# ArduinoNano33Proto-V2_0.net
KiCad netlist of a schematic drawn in EAGLE
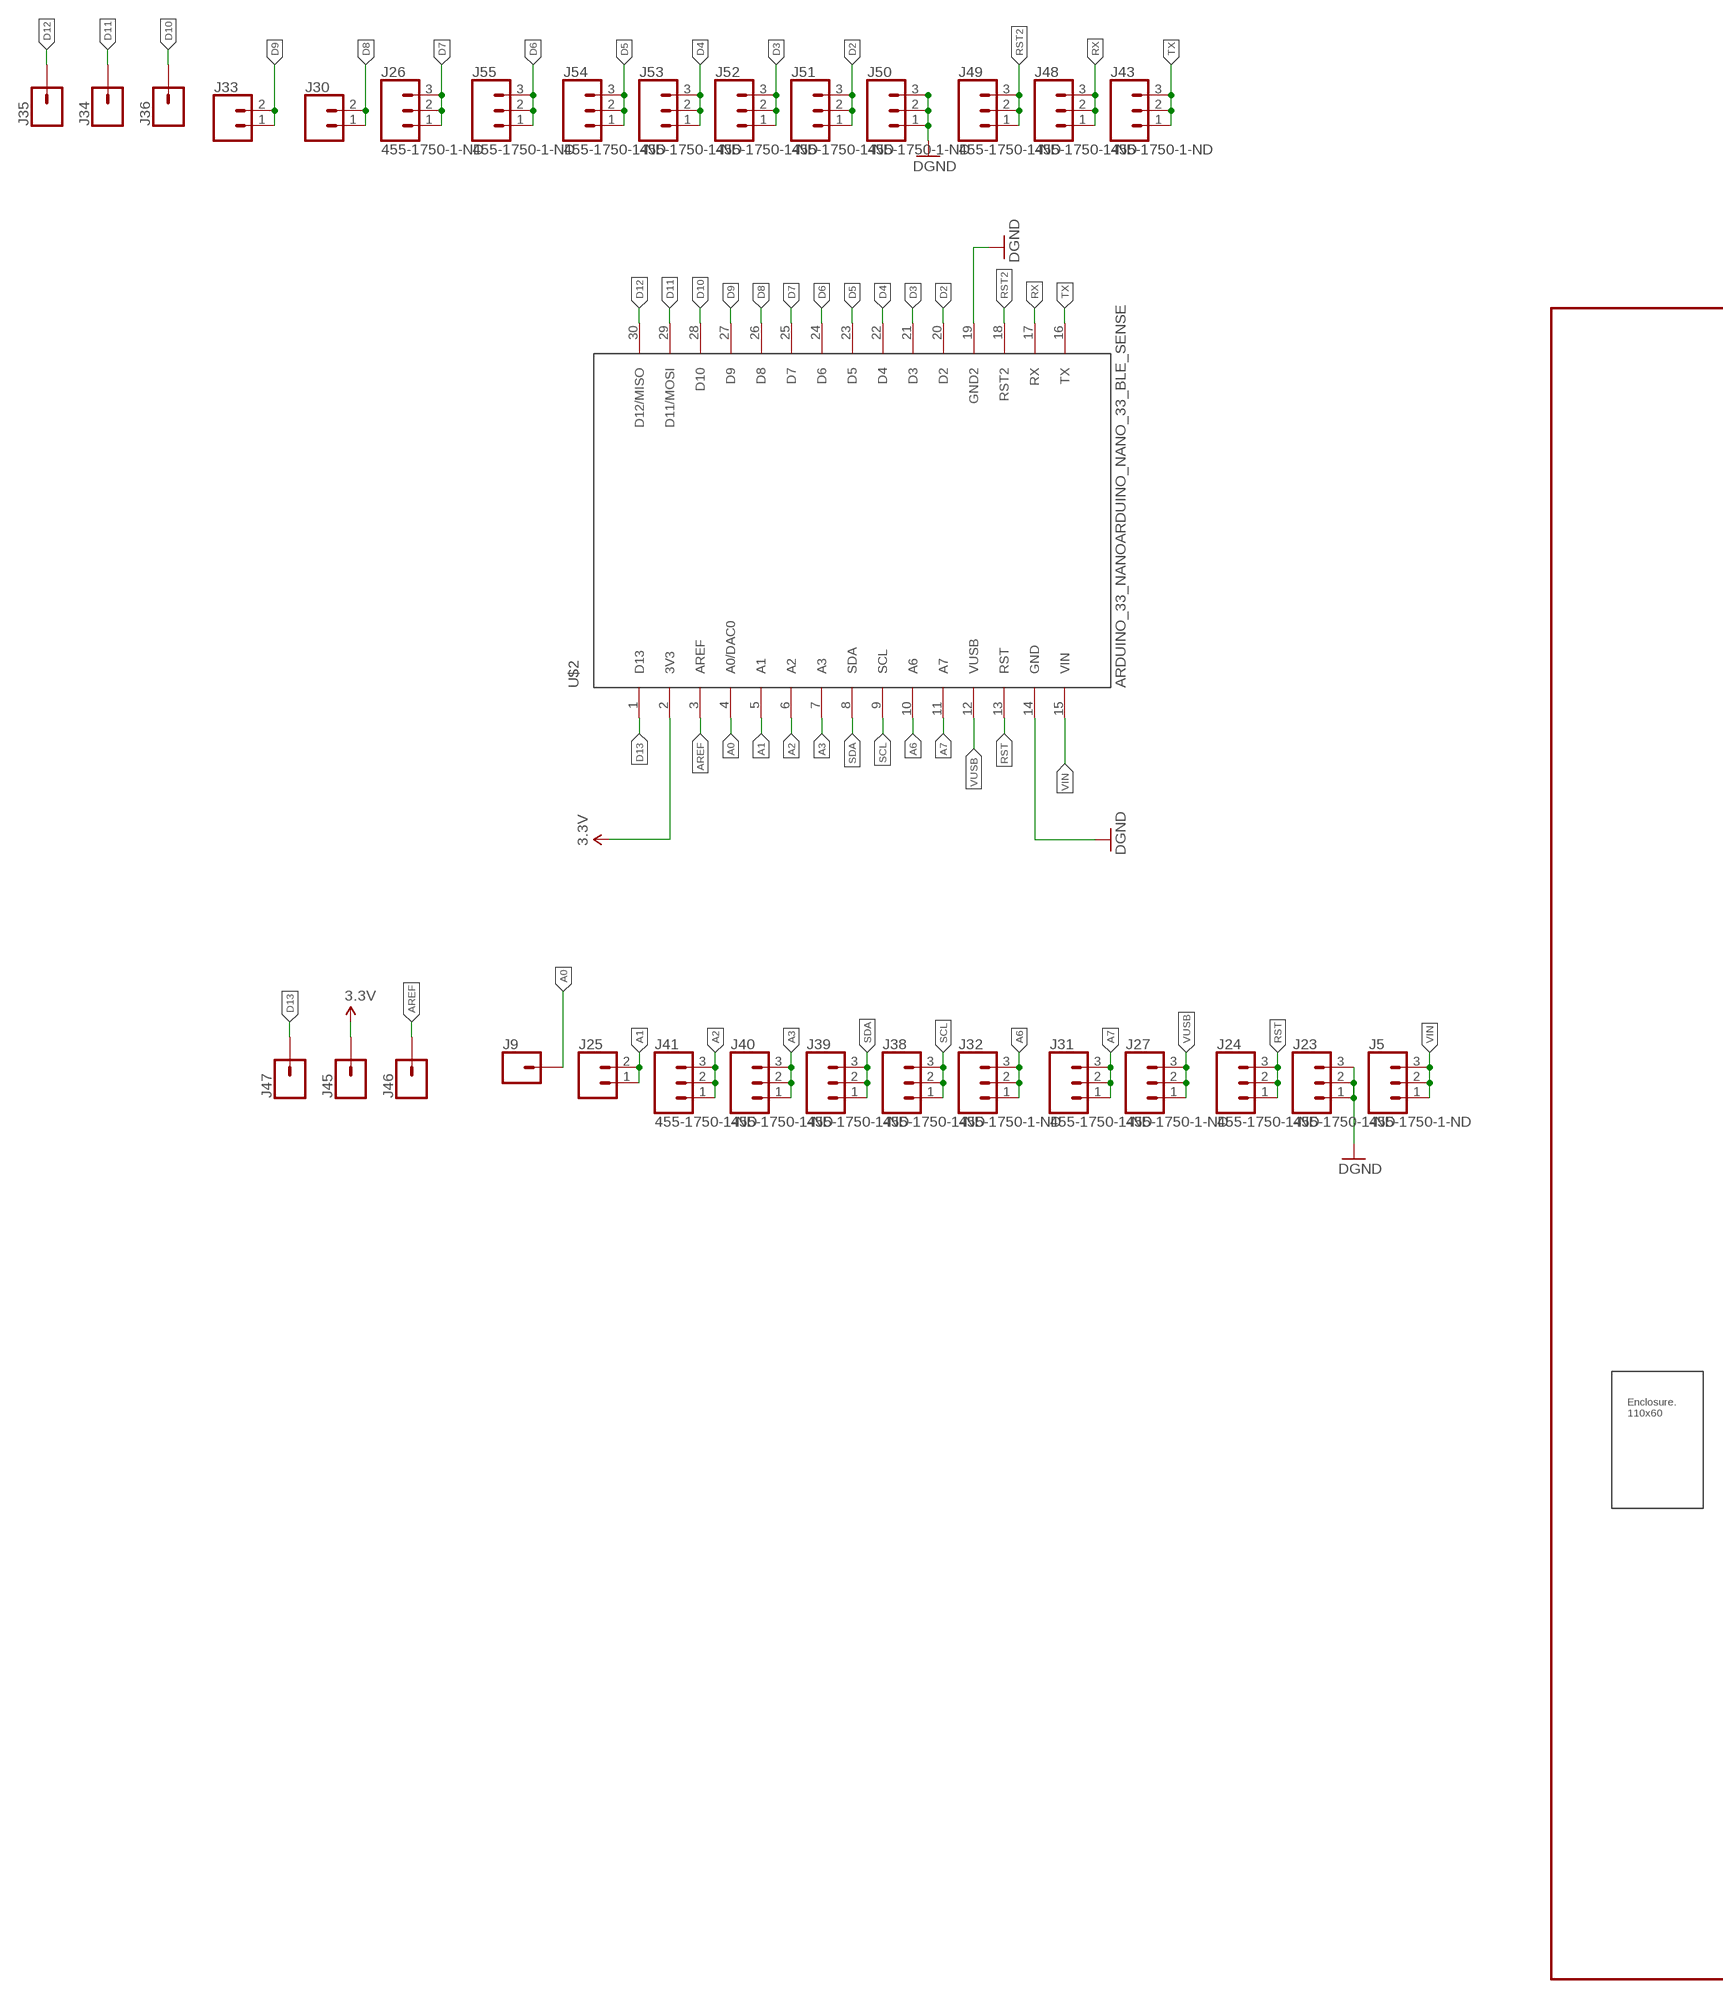
[diagram p0: schematic, sheet 1, part 1 of 2]
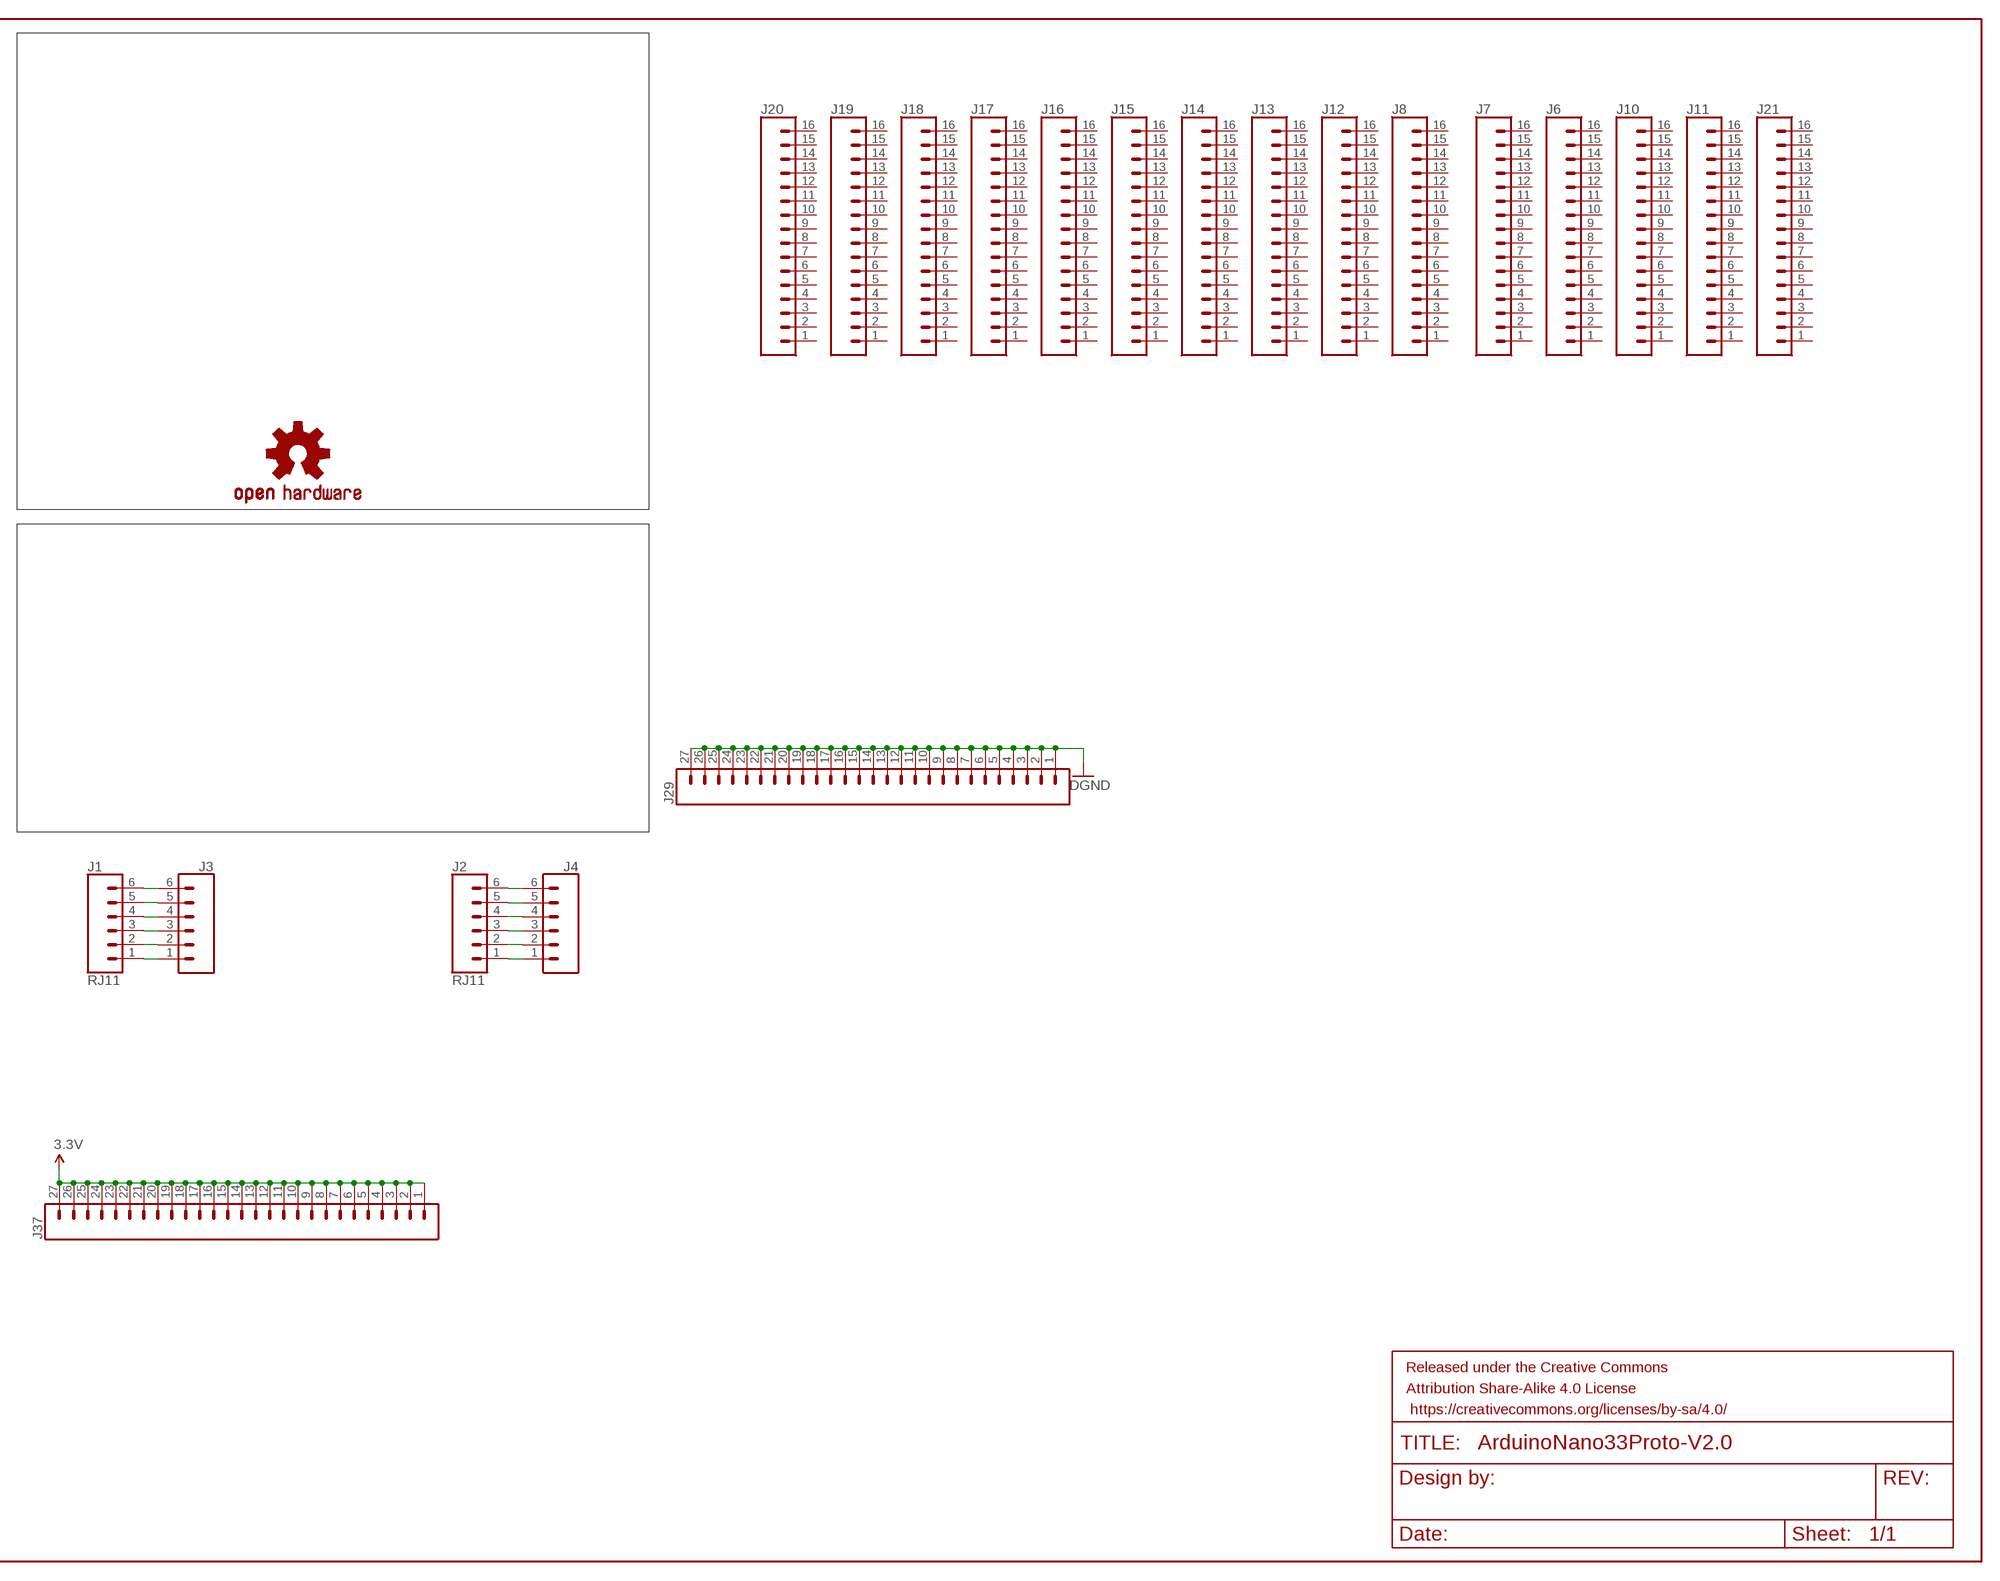
[diagram p1: schematic, sheet 1, part 2 of 2]

(export (version "E")
  (design (tool "Eeschema 10.0.6"))
  (components
    (comp (ref "FRAME2")
      (value "FRAME-LEDGER")
      (footprint "eagle-import:CREATIVE_COMMONS")
      (libsource (lib "eagle-import") (part "FRAME-LEDGER"))
    )
    (comp (ref "J1")
      (value "RJ11")
      (footprint "eagle-import:RJ11-6")
      (libsource (lib "eagle-import") (part "RJ11-6"))
    )
    (comp (ref "J2")
      (value "RJ11")
      (footprint "eagle-import:RJ11-6")
      (libsource (lib "eagle-import") (part "RJ11-6"))
    )
    (comp (ref "J3")
      (value "CONN_06SILK_FEMALE_PTH")
      (footprint "eagle-import:1X06")
      (libsource (lib "eagle-import") (part "CONN_06SILK_FEMALE_PTH"))
    )
    (comp (ref "J4")
      (value "CONN_06SILK_FEMALE_PTH")
      (footprint "eagle-import:1X06")
      (libsource (lib "eagle-import") (part "CONN_06SILK_FEMALE_PTH"))
    )
    (comp (ref "J5")
      (value "455-1750-1-ND")
      (footprint "eagle-import:1X03")
      (libsource (lib "eagle-import") (part "CONN_03"))
    )
    (comp (ref "J6")
      (value "CONN_161X16_NO_SILK")
      (footprint "eagle-import:1X16_NO_SILK")
      (libsource (lib "eagle-import") (part "CONN_161X16_NO_SILK"))
    )
    (comp (ref "J7")
      (value "CONN_161X16_NO_SILK")
      (footprint "eagle-import:1X16_NO_SILK")
      (libsource (lib "eagle-import") (part "CONN_161X16_NO_SILK"))
    )
    (comp (ref "J8")
      (value "CONN_161X16_NO_SILK")
      (footprint "eagle-import:1X16_NO_SILK")
      (libsource (lib "eagle-import") (part "CONN_161X16_NO_SILK"))
    )
    (comp (ref "J9")
      (value "CONN_01PTH_NO_SILK_YES_STOP")
      (footprint "eagle-import:1X01_NO_SILK")
      (libsource (lib "eagle-import") (part "CONN_01PTH_NO_SILK_YES_STOP"))
    )
    (comp (ref "J10")
      (value "CONN_161X16_NO_SILK")
      (footprint "eagle-import:1X16_NO_SILK")
      (libsource (lib "eagle-import") (part "CONN_161X16_NO_SILK"))
    )
    (comp (ref "J11")
      (value "CONN_161X16_NO_SILK")
      (footprint "eagle-import:1X16_NO_SILK")
      (libsource (lib "eagle-import") (part "CONN_161X16_NO_SILK"))
    )
    (comp (ref "J12")
      (value "CONN_161X16_NO_SILK")
      (footprint "eagle-import:1X16_NO_SILK")
      (libsource (lib "eagle-import") (part "CONN_161X16_NO_SILK"))
    )
    (comp (ref "J13")
      (value "CONN_161X16_NO_SILK")
      (footprint "eagle-import:1X16_NO_SILK")
      (libsource (lib "eagle-import") (part "CONN_161X16_NO_SILK"))
    )
    (comp (ref "J14")
      (value "CONN_161X16_NO_SILK")
      (footprint "eagle-import:1X16_NO_SILK")
      (libsource (lib "eagle-import") (part "CONN_161X16_NO_SILK"))
    )
    (comp (ref "J15")
      (value "CONN_161X16_NO_SILK")
      (footprint "eagle-import:1X16_NO_SILK")
      (libsource (lib "eagle-import") (part "CONN_161X16_NO_SILK"))
    )
    (comp (ref "J16")
      (value "CONN_161X16_NO_SILK")
      (footprint "eagle-import:1X16_NO_SILK")
      (libsource (lib "eagle-import") (part "CONN_161X16_NO_SILK"))
    )
    (comp (ref "J17")
      (value "CONN_161X16_NO_SILK")
      (footprint "eagle-import:1X16_NO_SILK")
      (libsource (lib "eagle-import") (part "CONN_161X16_NO_SILK"))
    )
    (comp (ref "J18")
      (value "CONN_161X16_NO_SILK")
      (footprint "eagle-import:1X16_NO_SILK")
      (libsource (lib "eagle-import") (part "CONN_161X16_NO_SILK"))
    )
    (comp (ref "J19")
      (value "CONN_161X16_NO_SILK")
      (footprint "eagle-import:1X16_NO_SILK")
      (libsource (lib "eagle-import") (part "CONN_161X16_NO_SILK"))
    )
    (comp (ref "J20")
      (value "CONN_161X16_NO_SILK")
      (footprint "eagle-import:1X16_NO_SILK")
      (libsource (lib "eagle-import") (part "CONN_161X16_NO_SILK"))
    )
    (comp (ref "J21")
      (value "CONN_161X16_NO_SILK")
      (footprint "eagle-import:1X16_NO_SILK")
      (libsource (lib "eagle-import") (part "CONN_161X16_NO_SILK"))
    )
    (comp (ref "J23")
      (value "455-1750-1-ND")
      (footprint "eagle-import:1X03")
      (libsource (lib "eagle-import") (part "CONN_03"))
    )
    (comp (ref "J24")
      (value "455-1750-1-ND")
      (footprint "eagle-import:1X03")
      (libsource (lib "eagle-import") (part "CONN_03"))
    )
    (comp (ref "J25")
      (value "CONN_02")
      (footprint "eagle-import:1X02")
      (libsource (lib "eagle-import") (part "CONN_02"))
    )
    (comp (ref "J26")
      (value "455-1750-1-ND")
      (footprint "eagle-import:1X03")
      (libsource (lib "eagle-import") (part "CONN_03"))
    )
    (comp (ref "J27")
      (value "455-1750-1-ND")
      (footprint "eagle-import:1X03")
      (libsource (lib "eagle-import") (part "CONN_03"))
    )
    (comp (ref "J29")
      (value "CONN_27")
      (footprint "eagle-import:1X27")
      (libsource (lib "eagle-import") (part "CONN_27"))
    )
    (comp (ref "J30")
      (value "CONN_02")
      (footprint "eagle-import:1X02")
      (libsource (lib "eagle-import") (part "CONN_02"))
    )
    (comp (ref "J31")
      (value "455-1750-1-ND")
      (footprint "eagle-import:1X03")
      (libsource (lib "eagle-import") (part "CONN_03"))
    )
    (comp (ref "J32")
      (value "455-1750-1-ND")
      (footprint "eagle-import:1X03")
      (libsource (lib "eagle-import") (part "CONN_03"))
    )
    (comp (ref "J33")
      (value "CONN_02")
      (footprint "eagle-import:1X02")
      (libsource (lib "eagle-import") (part "CONN_02"))
    )
    (comp (ref "J34")
      (value "CONN_01PTH_NO_SILK_YES_STOP")
      (footprint "eagle-import:1X01_NO_SILK")
      (libsource (lib "eagle-import") (part "CONN_01PTH_NO_SILK_YES_STOP"))
    )
    (comp (ref "J35")
      (value "CONN_01PTH_NO_SILK_YES_STOP")
      (footprint "eagle-import:1X01_NO_SILK")
      (libsource (lib "eagle-import") (part "CONN_01PTH_NO_SILK_YES_STOP"))
    )
    (comp (ref "J36")
      (value "CONN_01PTH_NO_SILK_YES_STOP")
      (footprint "eagle-import:1X01_NO_SILK")
      (libsource (lib "eagle-import") (part "CONN_01PTH_NO_SILK_YES_STOP"))
    )
    (comp (ref "J37")
      (value "CONN_27")
      (footprint "eagle-import:1X27")
      (libsource (lib "eagle-import") (part "CONN_27"))
    )
    (comp (ref "J38")
      (value "455-1750-1-ND")
      (footprint "eagle-import:1X03")
      (libsource (lib "eagle-import") (part "CONN_03"))
    )
    (comp (ref "J39")
      (value "455-1750-1-ND")
      (footprint "eagle-import:1X03")
      (libsource (lib "eagle-import") (part "CONN_03"))
    )
    (comp (ref "J40")
      (value "455-1750-1-ND")
      (footprint "eagle-import:1X03")
      (libsource (lib "eagle-import") (part "CONN_03"))
    )
    (comp (ref "J41")
      (value "455-1750-1-ND")
      (footprint "eagle-import:1X03")
      (libsource (lib "eagle-import") (part "CONN_03"))
    )
    (comp (ref "J43")
      (value "455-1750-1-ND")
      (footprint "eagle-import:1X03")
      (libsource (lib "eagle-import") (part "CONN_03"))
    )
    (comp (ref "J45")
      (value "CONN_01PTH_NO_SILK_YES_STOP")
      (footprint "eagle-import:1X01_NO_SILK")
      (libsource (lib "eagle-import") (part "CONN_01PTH_NO_SILK_YES_STOP"))
    )
    (comp (ref "J46")
      (value "CONN_01PTH_NO_SILK_YES_STOP")
      (footprint "eagle-import:1X01_NO_SILK")
      (libsource (lib "eagle-import") (part "CONN_01PTH_NO_SILK_YES_STOP"))
    )
    (comp (ref "J47")
      (value "CONN_01PTH_NO_SILK_YES_STOP")
      (footprint "eagle-import:1X01_NO_SILK")
      (libsource (lib "eagle-import") (part "CONN_01PTH_NO_SILK_YES_STOP"))
    )
    (comp (ref "J48")
      (value "455-1750-1-ND")
      (footprint "eagle-import:1X03")
      (libsource (lib "eagle-import") (part "CONN_03"))
    )
    (comp (ref "J49")
      (value "455-1750-1-ND")
      (footprint "eagle-import:1X03")
      (libsource (lib "eagle-import") (part "CONN_03"))
    )
    (comp (ref "J50")
      (value "455-1750-1-ND")
      (footprint "eagle-import:1X03")
      (libsource (lib "eagle-import") (part "CONN_03"))
    )
    (comp (ref "J51")
      (value "455-1750-1-ND")
      (footprint "eagle-import:1X03")
      (libsource (lib "eagle-import") (part "CONN_03"))
    )
    (comp (ref "J52")
      (value "455-1750-1-ND")
      (footprint "eagle-import:1X03")
      (libsource (lib "eagle-import") (part "CONN_03"))
    )
    (comp (ref "J53")
      (value "455-1750-1-ND")
      (footprint "eagle-import:1X03")
      (libsource (lib "eagle-import") (part "CONN_03"))
    )
    (comp (ref "J54")
      (value "455-1750-1-ND")
      (footprint "eagle-import:1X03")
      (libsource (lib "eagle-import") (part "CONN_03"))
    )
    (comp (ref "J55")
      (value "455-1750-1-ND")
      (footprint "eagle-import:1X03")
      (libsource (lib "eagle-import") (part "CONN_03"))
    )
    (comp (ref "LOGO1")
      (value "OSHW-LOGOM")
      (footprint "eagle-import:OSHW-LOGO-M")
      (libsource (lib "eagle-import") (part "OSHW-LOGOM"))
    )
    (comp (ref "U$1")
      (value "CAMDENBOSS-ENCLOSURE-110X60BOTH-EXTENDED-WIDE")
      (footprint "eagle-import:CAMDENBOSS_ENCLOSURE_110X60_WIDE_EXTENDED")
      (libsource (lib "eagle-import") (part "CAMDENBOSS-ENCLOSURE-110X60BOTH-EXTENDED-WIDE"))
    )
    (comp (ref "U$2")
      (value "ARDUINO_33_NANOARDUINO_NANO_33_BLE_SENSE")
      (footprint "eagle-import:ARDUINO_NANO_33")
      (libsource (lib "eagle-import") (part "ARDUINO_33_NANOARDUINO_NANO_33_BLE_SENSE"))
    )
  )
  (nets
    (net (code "1") (name "3.3V") (class "Default")
      (node (ref "J37") (pin "1") (pinfunction "1_1") (pintype "passive"))
      (node (ref "J37") (pin "10") (pinfunction "10_10") (pintype "passive"))
      (node (ref "J37") (pin "11") (pinfunction "11_11") (pintype "passive"))
      (node (ref "J37") (pin "12") (pinfunction "12_12") (pintype "passive"))
      (node (ref "J37") (pin "13") (pinfunction "13_13") (pintype "passive"))
      (node (ref "J37") (pin "14") (pinfunction "14_14") (pintype "passive"))
      (node (ref "J37") (pin "15") (pinfunction "15_15") (pintype "passive"))
      (node (ref "J37") (pin "16") (pinfunction "16_16") (pintype "passive"))
      (node (ref "J37") (pin "17") (pinfunction "17_17") (pintype "passive"))
      (node (ref "J37") (pin "18") (pinfunction "18_18") (pintype "passive"))
      (node (ref "J37") (pin "19") (pinfunction "19_19") (pintype "passive"))
      (node (ref "J37") (pin "2") (pinfunction "2_2") (pintype "passive"))
      (node (ref "J37") (pin "20") (pinfunction "20_20") (pintype "passive"))
      (node (ref "J37") (pin "21") (pinfunction "21_21") (pintype "passive"))
      (node (ref "J37") (pin "22") (pinfunction "22_22") (pintype "passive"))
      (node (ref "J37") (pin "23") (pinfunction "23_23") (pintype "passive"))
      (node (ref "J37") (pin "24") (pinfunction "24_24") (pintype "passive"))
      (node (ref "J37") (pin "25") (pinfunction "25_25") (pintype "passive"))
      (node (ref "J37") (pin "26") (pinfunction "26_26") (pintype "passive"))
      (node (ref "J37") (pin "27") (pinfunction "27_27") (pintype "passive"))
      (node (ref "J37") (pin "3") (pinfunction "3_3") (pintype "passive"))
      (node (ref "J37") (pin "4") (pinfunction "4_4") (pintype "passive"))
      (node (ref "J37") (pin "5") (pinfunction "5_5") (pintype "passive"))
      (node (ref "J37") (pin "6") (pinfunction "6_6") (pintype "passive"))
      (node (ref "J37") (pin "7") (pinfunction "7_7") (pintype "passive"))
      (node (ref "J37") (pin "8") (pinfunction "8_8") (pintype "passive"))
      (node (ref "J37") (pin "9") (pinfunction "9_9") (pintype "passive"))
      (node (ref "J45") (pin "1") (pinfunction "1_1") (pintype "passive"))
      (node (ref "U$2") (pin "2") (pinfunction "3V3_2") (pintype "power_in"))
    )
    (net (code "2") (name "A0") (class "Default")
      (node (ref "J9") (pin "1") (pinfunction "1_1") (pintype "passive"))
      (node (ref "U$2") (pin "4") (pinfunction "A0/DAC0_4") (pintype "bidirectional"))
    )
    (net (code "3") (name "A1") (class "Default")
      (node (ref "J25") (pin "1") (pinfunction "1_1") (pintype "passive"))
      (node (ref "J25") (pin "2") (pinfunction "2_2") (pintype "passive"))
      (node (ref "U$2") (pin "5") (pinfunction "A1_5") (pintype "bidirectional"))
    )
    (net (code "4") (name "A2") (class "Default")
      (node (ref "J41") (pin "1") (pinfunction "1_1") (pintype "passive"))
      (node (ref "J41") (pin "2") (pinfunction "2_2") (pintype "passive"))
      (node (ref "J41") (pin "3") (pinfunction "3_3") (pintype "passive"))
      (node (ref "U$2") (pin "6") (pinfunction "A2_6") (pintype "bidirectional"))
    )
    (net (code "5") (name "A3") (class "Default")
      (node (ref "J40") (pin "1") (pinfunction "1_1") (pintype "passive"))
      (node (ref "J40") (pin "2") (pinfunction "2_2") (pintype "passive"))
      (node (ref "J40") (pin "3") (pinfunction "3_3") (pintype "passive"))
      (node (ref "U$2") (pin "7") (pinfunction "A3_7") (pintype "bidirectional"))
    )
    (net (code "6") (name "A6") (class "Default")
      (node (ref "J32") (pin "1") (pinfunction "1_1") (pintype "passive"))
      (node (ref "J32") (pin "2") (pinfunction "2_2") (pintype "passive"))
      (node (ref "J32") (pin "3") (pinfunction "3_3") (pintype "passive"))
      (node (ref "U$2") (pin "10") (pinfunction "A6_10") (pintype "bidirectional"))
    )
    (net (code "7") (name "A7") (class "Default")
      (node (ref "J31") (pin "1") (pinfunction "1_1") (pintype "passive"))
      (node (ref "J31") (pin "2") (pinfunction "2_2") (pintype "passive"))
      (node (ref "J31") (pin "3") (pinfunction "3_3") (pintype "passive"))
      (node (ref "U$2") (pin "11") (pinfunction "A7_11") (pintype "bidirectional"))
    )
    (net (code "8") (name "AREF") (class "Default")
      (node (ref "J46") (pin "1") (pinfunction "1_1") (pintype "passive"))
      (node (ref "U$2") (pin "3") (pinfunction "AREF_3") (pintype "output"))
    )
    (net (code "9") (name "D2") (class "Default")
      (node (ref "J51") (pin "1") (pinfunction "1_1") (pintype "passive"))
      (node (ref "J51") (pin "2") (pinfunction "2_2") (pintype "passive"))
      (node (ref "J51") (pin "3") (pinfunction "3_3") (pintype "passive"))
      (node (ref "U$2") (pin "20") (pinfunction "D2_20") (pintype "bidirectional"))
    )
    (net (code "10") (name "D3") (class "Default")
      (node (ref "J52") (pin "1") (pinfunction "1_1") (pintype "passive"))
      (node (ref "J52") (pin "2") (pinfunction "2_2") (pintype "passive"))
      (node (ref "J52") (pin "3") (pinfunction "3_3") (pintype "passive"))
      (node (ref "U$2") (pin "21") (pinfunction "D3_21") (pintype "bidirectional"))
    )
    (net (code "11") (name "D4") (class "Default")
      (node (ref "J53") (pin "1") (pinfunction "1_1") (pintype "passive"))
      (node (ref "J53") (pin "2") (pinfunction "2_2") (pintype "passive"))
      (node (ref "J53") (pin "3") (pinfunction "3_3") (pintype "passive"))
      (node (ref "U$2") (pin "22") (pinfunction "D4_22") (pintype "bidirectional"))
    )
    (net (code "12") (name "D5") (class "Default")
      (node (ref "J54") (pin "1") (pinfunction "1_1") (pintype "passive"))
      (node (ref "J54") (pin "2") (pinfunction "2_2") (pintype "passive"))
      (node (ref "J54") (pin "3") (pinfunction "3_3") (pintype "passive"))
      (node (ref "U$2") (pin "23") (pinfunction "D5_23") (pintype "bidirectional"))
    )
    (net (code "13") (name "D6") (class "Default")
      (node (ref "J55") (pin "1") (pinfunction "1_1") (pintype "passive"))
      (node (ref "J55") (pin "2") (pinfunction "2_2") (pintype "passive"))
      (node (ref "J55") (pin "3") (pinfunction "3_3") (pintype "passive"))
      (node (ref "U$2") (pin "24") (pinfunction "D6_24") (pintype "bidirectional"))
    )
    (net (code "14") (name "D7") (class "Default")
      (node (ref "J26") (pin "1") (pinfunction "1_1") (pintype "passive"))
      (node (ref "J26") (pin "2") (pinfunction "2_2") (pintype "passive"))
      (node (ref "J26") (pin "3") (pinfunction "3_3") (pintype "passive"))
      (node (ref "U$2") (pin "25") (pinfunction "D7_25") (pintype "bidirectional"))
    )
    (net (code "15") (name "D8") (class "Default")
      (node (ref "J30") (pin "1") (pinfunction "1_1") (pintype "passive"))
      (node (ref "J30") (pin "2") (pinfunction "2_2") (pintype "passive"))
      (node (ref "U$2") (pin "26") (pinfunction "D8_26") (pintype "bidirectional"))
    )
    (net (code "16") (name "D9") (class "Default")
      (node (ref "J33") (pin "1") (pinfunction "1_1") (pintype "passive"))
      (node (ref "J33") (pin "2") (pinfunction "2_2") (pintype "passive"))
      (node (ref "U$2") (pin "27") (pinfunction "D9_27") (pintype "bidirectional"))
    )
    (net (code "17") (name "D10") (class "Default")
      (node (ref "J36") (pin "1") (pinfunction "1_1") (pintype "passive"))
      (node (ref "U$2") (pin "28") (pinfunction "D10_28") (pintype "bidirectional"))
    )
    (net (code "18") (name "D11") (class "Default")
      (node (ref "J34") (pin "1") (pinfunction "1_1") (pintype "passive"))
      (node (ref "U$2") (pin "29") (pinfunction "D11/MOSI_29") (pintype "bidirectional"))
    )
    (net (code "19") (name "D12") (class "Default")
      (node (ref "J35") (pin "1") (pinfunction "1_1") (pintype "passive"))
      (node (ref "U$2") (pin "30") (pinfunction "D12/MISO_30") (pintype "bidirectional"))
    )
    (net (code "20") (name "D13") (class "Default")
      (node (ref "J47") (pin "1") (pinfunction "1_1") (pintype "passive"))
      (node (ref "U$2") (pin "1") (pinfunction "D13_1") (pintype "bidirectional"))
    )
    (net (code "21") (name "DGND") (class "Default")
      (node (ref "J23") (pin "1") (pinfunction "1_1") (pintype "passive"))
      (node (ref "J23") (pin "2") (pinfunction "2_2") (pintype "passive"))
      (node (ref "J23") (pin "3") (pinfunction "3_3") (pintype "passive"))
      (node (ref "J29") (pin "1") (pinfunction "1_1") (pintype "passive"))
      (node (ref "J29") (pin "10") (pinfunction "10_10") (pintype "passive"))
      (node (ref "J29") (pin "11") (pinfunction "11_11") (pintype "passive"))
      (node (ref "J29") (pin "12") (pinfunction "12_12") (pintype "passive"))
      (node (ref "J29") (pin "13") (pinfunction "13_13") (pintype "passive"))
      (node (ref "J29") (pin "14") (pinfunction "14_14") (pintype "passive"))
      (node (ref "J29") (pin "15") (pinfunction "15_15") (pintype "passive"))
      (node (ref "J29") (pin "16") (pinfunction "16_16") (pintype "passive"))
      (node (ref "J29") (pin "17") (pinfunction "17_17") (pintype "passive"))
      (node (ref "J29") (pin "18") (pinfunction "18_18") (pintype "passive"))
      (node (ref "J29") (pin "19") (pinfunction "19_19") (pintype "passive"))
      (node (ref "J29") (pin "2") (pinfunction "2_2") (pintype "passive"))
      (node (ref "J29") (pin "20") (pinfunction "20_20") (pintype "passive"))
      (node (ref "J29") (pin "21") (pinfunction "21_21") (pintype "passive"))
      (node (ref "J29") (pin "22") (pinfunction "22_22") (pintype "passive"))
      (node (ref "J29") (pin "23") (pinfunction "23_23") (pintype "passive"))
      (node (ref "J29") (pin "24") (pinfunction "24_24") (pintype "passive"))
      (node (ref "J29") (pin "25") (pinfunction "25_25") (pintype "passive"))
      (node (ref "J29") (pin "26") (pinfunction "26_26") (pintype "passive"))
      (node (ref "J29") (pin "27") (pinfunction "27_27") (pintype "passive"))
      (node (ref "J29") (pin "3") (pinfunction "3_3") (pintype "passive"))
      (node (ref "J29") (pin "4") (pinfunction "4_4") (pintype "passive"))
      (node (ref "J29") (pin "5") (pinfunction "5_5") (pintype "passive"))
      (node (ref "J29") (pin "6") (pinfunction "6_6") (pintype "passive"))
      (node (ref "J29") (pin "7") (pinfunction "7_7") (pintype "passive"))
      (node (ref "J29") (pin "8") (pinfunction "8_8") (pintype "passive"))
      (node (ref "J29") (pin "9") (pinfunction "9_9") (pintype "passive"))
      (node (ref "J50") (pin "1") (pinfunction "1_1") (pintype "passive"))
      (node (ref "J50") (pin "2") (pinfunction "2_2") (pintype "passive"))
      (node (ref "J50") (pin "3") (pinfunction "3_3") (pintype "passive"))
      (node (ref "U$2") (pin "14") (pinfunction "GND_14") (pintype "bidirectional"))
      (node (ref "U$2") (pin "19") (pinfunction "GND2_19") (pintype "bidirectional"))
    )
    (net (code "22") (name "Net-(J1-Pad1)") (class "Default")
      (node (ref "J1") (pin "1") (pinfunction "1_1") (pintype "passive"))
      (node (ref "J3") (pin "1") (pinfunction "1_1") (pintype "passive"))
    )
    (net (code "23") (name "Net-(J1-Pad2)") (class "Default")
      (node (ref "J1") (pin "2") (pinfunction "2_2") (pintype "passive"))
      (node (ref "J3") (pin "2") (pinfunction "2_2") (pintype "passive"))
    )
    (net (code "24") (name "Net-(J1-Pad3)") (class "Default")
      (node (ref "J1") (pin "3") (pinfunction "3_3") (pintype "passive"))
      (node (ref "J3") (pin "3") (pinfunction "3_3") (pintype "passive"))
    )
    (net (code "25") (name "Net-(J1-Pad4)") (class "Default")
      (node (ref "J1") (pin "4") (pinfunction "4_4") (pintype "passive"))
      (node (ref "J3") (pin "4") (pinfunction "4_4") (pintype "passive"))
    )
    (net (code "26") (name "Net-(J1-Pad5)") (class "Default")
      (node (ref "J1") (pin "5") (pinfunction "5_5") (pintype "passive"))
      (node (ref "J3") (pin "5") (pinfunction "5_5") (pintype "passive"))
    )
    (net (code "27") (name "Net-(J1-Pad6)") (class "Default")
      (node (ref "J1") (pin "6") (pinfunction "6_6") (pintype "passive"))
      (node (ref "J3") (pin "6") (pinfunction "6_6") (pintype "passive"))
    )
    (net (code "28") (name "Net-(J2-Pad1)") (class "Default")
      (node (ref "J2") (pin "1") (pinfunction "1_1") (pintype "passive"))
      (node (ref "J4") (pin "1") (pinfunction "1_1") (pintype "passive"))
    )
    (net (code "29") (name "Net-(J2-Pad2)") (class "Default")
      (node (ref "J2") (pin "2") (pinfunction "2_2") (pintype "passive"))
      (node (ref "J4") (pin "2") (pinfunction "2_2") (pintype "passive"))
    )
    (net (code "30") (name "Net-(J2-Pad3)") (class "Default")
      (node (ref "J2") (pin "3") (pinfunction "3_3") (pintype "passive"))
      (node (ref "J4") (pin "3") (pinfunction "3_3") (pintype "passive"))
    )
    (net (code "31") (name "Net-(J2-Pad4)") (class "Default")
      (node (ref "J2") (pin "4") (pinfunction "4_4") (pintype "passive"))
      (node (ref "J4") (pin "4") (pinfunction "4_4") (pintype "passive"))
    )
    (net (code "32") (name "Net-(J2-Pad5)") (class "Default")
      (node (ref "J2") (pin "5") (pinfunction "5_5") (pintype "passive"))
      (node (ref "J4") (pin "5") (pinfunction "5_5") (pintype "passive"))
    )
    (net (code "33") (name "Net-(J2-Pad6)") (class "Default")
      (node (ref "J2") (pin "6") (pinfunction "6_6") (pintype "passive"))
      (node (ref "J4") (pin "6") (pinfunction "6_6") (pintype "passive"))
    )
    (net (code "34") (name "RST") (class "Default")
      (node (ref "J24") (pin "1") (pinfunction "1_1") (pintype "passive"))
      (node (ref "J24") (pin "2") (pinfunction "2_2") (pintype "passive"))
      (node (ref "J24") (pin "3") (pinfunction "3_3") (pintype "passive"))
      (node (ref "U$2") (pin "13") (pinfunction "RST_13") (pintype "bidirectional"))
    )
    (net (code "35") (name "RST2") (class "Default")
      (node (ref "J49") (pin "1") (pinfunction "1_1") (pintype "passive"))
      (node (ref "J49") (pin "2") (pinfunction "2_2") (pintype "passive"))
      (node (ref "J49") (pin "3") (pinfunction "3_3") (pintype "passive"))
      (node (ref "U$2") (pin "18") (pinfunction "RST2_18") (pintype "bidirectional"))
    )
    (net (code "36") (name "RX") (class "Default")
      (node (ref "J48") (pin "1") (pinfunction "1_1") (pintype "passive"))
      (node (ref "J48") (pin "2") (pinfunction "2_2") (pintype "passive"))
      (node (ref "J48") (pin "3") (pinfunction "3_3") (pintype "passive"))
      (node (ref "U$2") (pin "17") (pinfunction "RX_17") (pintype "bidirectional"))
    )
    (net (code "37") (name "SCL") (class "Default")
      (node (ref "J38") (pin "1") (pinfunction "1_1") (pintype "passive"))
      (node (ref "J38") (pin "2") (pinfunction "2_2") (pintype "passive"))
      (node (ref "J38") (pin "3") (pinfunction "3_3") (pintype "passive"))
      (node (ref "U$2") (pin "9") (pinfunction "SCL_9") (pintype "bidirectional"))
    )
    (net (code "38") (name "SDA") (class "Default")
      (node (ref "J39") (pin "1") (pinfunction "1_1") (pintype "passive"))
      (node (ref "J39") (pin "2") (pinfunction "2_2") (pintype "passive"))
      (node (ref "J39") (pin "3") (pinfunction "3_3") (pintype "passive"))
      (node (ref "U$2") (pin "8") (pinfunction "SDA_8") (pintype "bidirectional"))
    )
    (net (code "39") (name "TX") (class "Default")
      (node (ref "J43") (pin "1") (pinfunction "1_1") (pintype "passive"))
      (node (ref "J43") (pin "2") (pinfunction "2_2") (pintype "passive"))
      (node (ref "J43") (pin "3") (pinfunction "3_3") (pintype "passive"))
      (node (ref "U$2") (pin "16") (pinfunction "TX_16") (pintype "bidirectional"))
    )
    (net (code "40") (name "VIN") (class "Default")
      (node (ref "J5") (pin "1") (pinfunction "1_1") (pintype "passive"))
      (node (ref "J5") (pin "2") (pinfunction "2_2") (pintype "passive"))
      (node (ref "J5") (pin "3") (pinfunction "3_3") (pintype "passive"))
      (node (ref "U$2") (pin "15") (pinfunction "VIN_15") (pintype "power_in"))
    )
    (net (code "41") (name "VUSB") (class "Default")
      (node (ref "J27") (pin "1") (pinfunction "1_1") (pintype "passive"))
      (node (ref "J27") (pin "2") (pinfunction "2_2") (pintype "passive"))
      (node (ref "J27") (pin "3") (pinfunction "3_3") (pintype "passive"))
      (node (ref "U$2") (pin "12") (pinfunction "VUSB_12") (pintype "power_in"))
    )
    (net (code "42") (name "unconnected-(J6-Pad1)") (class "Default")
      (node (ref "J6") (pin "1") (pinfunction "1_1") (pintype "passive"))
    )
    (net (code "43") (name "unconnected-(J6-Pad2)") (class "Default")
      (node (ref "J6") (pin "2") (pinfunction "2_2") (pintype "passive"))
    )
    (net (code "44") (name "unconnected-(J6-Pad3)") (class "Default")
      (node (ref "J6") (pin "3") (pinfunction "3_3") (pintype "passive"))
    )
    (net (code "45") (name "unconnected-(J6-Pad4)") (class "Default")
      (node (ref "J6") (pin "4") (pinfunction "4_4") (pintype "passive"))
    )
    (net (code "46") (name "unconnected-(J6-Pad5)") (class "Default")
      (node (ref "J6") (pin "5") (pinfunction "5_5") (pintype "passive"))
    )
    (net (code "47") (name "unconnected-(J6-Pad6)") (class "Default")
      (node (ref "J6") (pin "6") (pinfunction "6_6") (pintype "passive"))
    )
    (net (code "48") (name "unconnected-(J6-Pad7)") (class "Default")
      (node (ref "J6") (pin "7") (pinfunction "7_7") (pintype "passive"))
    )
    (net (code "49") (name "unconnected-(J6-Pad8)") (class "Default")
      (node (ref "J6") (pin "8") (pinfunction "8_8") (pintype "passive"))
    )
    (net (code "50") (name "unconnected-(J6-Pad9)") (class "Default")
      (node (ref "J6") (pin "9") (pinfunction "9_9") (pintype "passive"))
    )
    (net (code "51") (name "unconnected-(J6-Pad10)") (class "Default")
      (node (ref "J6") (pin "10") (pinfunction "10_10") (pintype "passive"))
    )
    (net (code "52") (name "unconnected-(J6-Pad11)") (class "Default")
      (node (ref "J6") (pin "11") (pinfunction "11_11") (pintype "passive"))
    )
    (net (code "53") (name "unconnected-(J6-Pad12)") (class "Default")
      (node (ref "J6") (pin "12") (pinfunction "12_12") (pintype "passive"))
    )
    (net (code "54") (name "unconnected-(J6-Pad13)") (class "Default")
      (node (ref "J6") (pin "13") (pinfunction "13_13") (pintype "passive"))
    )
    (net (code "55") (name "unconnected-(J6-Pad14)") (class "Default")
      (node (ref "J6") (pin "14") (pinfunction "14_14") (pintype "passive"))
    )
    (net (code "56") (name "unconnected-(J6-Pad15)") (class "Default")
      (node (ref "J6") (pin "15") (pinfunction "15_15") (pintype "passive"))
    )
    (net (code "57") (name "unconnected-(J6-Pad16)") (class "Default")
      (node (ref "J6") (pin "16") (pinfunction "16_16") (pintype "passive"))
    )
    (net (code "58") (name "unconnected-(J7-Pad1)") (class "Default")
      (node (ref "J7") (pin "1") (pinfunction "1_1") (pintype "passive"))
    )
    (net (code "59") (name "unconnected-(J7-Pad2)") (class "Default")
      (node (ref "J7") (pin "2") (pinfunction "2_2") (pintype "passive"))
    )
    (net (code "60") (name "unconnected-(J7-Pad3)") (class "Default")
      (node (ref "J7") (pin "3") (pinfunction "3_3") (pintype "passive"))
    )
    (net (code "61") (name "unconnected-(J7-Pad4)") (class "Default")
      (node (ref "J7") (pin "4") (pinfunction "4_4") (pintype "passive"))
    )
    (net (code "62") (name "unconnected-(J7-Pad5)") (class "Default")
      (node (ref "J7") (pin "5") (pinfunction "5_5") (pintype "passive"))
    )
    (net (code "63") (name "unconnected-(J7-Pad6)") (class "Default")
      (node (ref "J7") (pin "6") (pinfunction "6_6") (pintype "passive"))
    )
    (net (code "64") (name "unconnected-(J7-Pad7)") (class "Default")
      (node (ref "J7") (pin "7") (pinfunction "7_7") (pintype "passive"))
    )
    (net (code "65") (name "unconnected-(J7-Pad8)") (class "Default")
      (node (ref "J7") (pin "8") (pinfunction "8_8") (pintype "passive"))
    )
    (net (code "66") (name "unconnected-(J7-Pad9)") (class "Default")
      (node (ref "J7") (pin "9") (pinfunction "9_9") (pintype "passive"))
    )
    (net (code "67") (name "unconnected-(J7-Pad10)") (class "Default")
      (node (ref "J7") (pin "10") (pinfunction "10_10") (pintype "passive"))
    )
    (net (code "68") (name "unconnected-(J7-Pad11)") (class "Default")
      (node (ref "J7") (pin "11") (pinfunction "11_11") (pintype "passive"))
    )
    (net (code "69") (name "unconnected-(J7-Pad12)") (class "Default")
      (node (ref "J7") (pin "12") (pinfunction "12_12") (pintype "passive"))
    )
    (net (code "70") (name "unconnected-(J7-Pad13)") (class "Default")
      (node (ref "J7") (pin "13") (pinfunction "13_13") (pintype "passive"))
    )
    (net (code "71") (name "unconnected-(J7-Pad14)") (class "Default")
      (node (ref "J7") (pin "14") (pinfunction "14_14") (pintype "passive"))
    )
    (net (code "72") (name "unconnected-(J7-Pad15)") (class "Default")
      (node (ref "J7") (pin "15") (pinfunction "15_15") (pintype "passive"))
    )
    (net (code "73") (name "unconnected-(J7-Pad16)") (class "Default")
      (node (ref "J7") (pin "16") (pinfunction "16_16") (pintype "passive"))
    )
    (net (code "74") (name "unconnected-(J8-Pad1)") (class "Default")
      (node (ref "J8") (pin "1") (pinfunction "1_1") (pintype "passive"))
    )
    (net (code "75") (name "unconnected-(J8-Pad2)") (class "Default")
      (node (ref "J8") (pin "2") (pinfunction "2_2") (pintype "passive"))
    )
    (net (code "76") (name "unconnected-(J8-Pad3)") (class "Default")
      (node (ref "J8") (pin "3") (pinfunction "3_3") (pintype "passive"))
    )
    (net (code "77") (name "unconnected-(J8-Pad4)") (class "Default")
      (node (ref "J8") (pin "4") (pinfunction "4_4") (pintype "passive"))
    )
    (net (code "78") (name "unconnected-(J8-Pad5)") (class "Default")
      (node (ref "J8") (pin "5") (pinfunction "5_5") (pintype "passive"))
    )
    (net (code "79") (name "unconnected-(J8-Pad6)") (class "Default")
      (node (ref "J8") (pin "6") (pinfunction "6_6") (pintype "passive"))
    )
    (net (code "80") (name "unconnected-(J8-Pad7)") (class "Default")
      (node (ref "J8") (pin "7") (pinfunction "7_7") (pintype "passive"))
    )
    (net (code "81") (name "unconnected-(J8-Pad8)") (class "Default")
      (node (ref "J8") (pin "8") (pinfunction "8_8") (pintype "passive"))
    )
    (net (code "82") (name "unconnected-(J8-Pad9)") (class "Default")
      (node (ref "J8") (pin "9") (pinfunction "9_9") (pintype "passive"))
    )
    (net (code "83") (name "unconnected-(J8-Pad10)") (class "Default")
      (node (ref "J8") (pin "10") (pinfunction "10_10") (pintype "passive"))
    )
    (net (code "84") (name "unconnected-(J8-Pad11)") (class "Default")
      (node (ref "J8") (pin "11") (pinfunction "11_11") (pintype "passive"))
    )
    (net (code "85") (name "unconnected-(J8-Pad12)") (class "Default")
      (node (ref "J8") (pin "12") (pinfunction "12_12") (pintype "passive"))
    )
    (net (code "86") (name "unconnected-(J8-Pad13)") (class "Default")
      (node (ref "J8") (pin "13") (pinfunction "13_13") (pintype "passive"))
    )
    (net (code "87") (name "unconnected-(J8-Pad14)") (class "Default")
      (node (ref "J8") (pin "14") (pinfunction "14_14") (pintype "passive"))
    )
    (net (code "88") (name "unconnected-(J8-Pad15)") (class "Default")
      (node (ref "J8") (pin "15") (pinfunction "15_15") (pintype "passive"))
    )
    (net (code "89") (name "unconnected-(J8-Pad16)") (class "Default")
      (node (ref "J8") (pin "16") (pinfunction "16_16") (pintype "passive"))
    )
    (net (code "90") (name "unconnected-(J10-Pad1)") (class "Default")
      (node (ref "J10") (pin "1") (pinfunction "1_1") (pintype "passive"))
    )
    (net (code "91") (name "unconnected-(J10-Pad2)") (class "Default")
      (node (ref "J10") (pin "2") (pinfunction "2_2") (pintype "passive"))
    )
    (net (code "92") (name "unconnected-(J10-Pad3)") (class "Default")
      (node (ref "J10") (pin "3") (pinfunction "3_3") (pintype "passive"))
    )
    (net (code "93") (name "unconnected-(J10-Pad4)") (class "Default")
      (node (ref "J10") (pin "4") (pinfunction "4_4") (pintype "passive"))
    )
    (net (code "94") (name "unconnected-(J10-Pad5)") (class "Default")
      (node (ref "J10") (pin "5") (pinfunction "5_5") (pintype "passive"))
    )
    (net (code "95") (name "unconnected-(J10-Pad6)") (class "Default")
      (node (ref "J10") (pin "6") (pinfunction "6_6") (pintype "passive"))
    )
    (net (code "96") (name "unconnected-(J10-Pad7)") (class "Default")
      (node (ref "J10") (pin "7") (pinfunction "7_7") (pintype "passive"))
    )
    (net (code "97") (name "unconnected-(J10-Pad8)") (class "Default")
      (node (ref "J10") (pin "8") (pinfunction "8_8") (pintype "passive"))
    )
    (net (code "98") (name "unconnected-(J10-Pad9)") (class "Default")
      (node (ref "J10") (pin "9") (pinfunction "9_9") (pintype "passive"))
    )
    (net (code "99") (name "unconnected-(J10-Pad10)") (class "Default")
      (node (ref "J10") (pin "10") (pinfunction "10_10") (pintype "passive"))
    )
    (net (code "100") (name "unconnected-(J10-Pad11)") (class "Default")
      (node (ref "J10") (pin "11") (pinfunction "11_11") (pintype "passive"))
    )
    (net (code "101") (name "unconnected-(J10-Pad12)") (class "Default")
      (node (ref "J10") (pin "12") (pinfunction "12_12") (pintype "passive"))
    )
    (net (code "102") (name "unconnected-(J10-Pad13)") (class "Default")
      (node (ref "J10") (pin "13") (pinfunction "13_13") (pintype "passive"))
    )
    (net (code "103") (name "unconnected-(J10-Pad14)") (class "Default")
      (node (ref "J10") (pin "14") (pinfunction "14_14") (pintype "passive"))
    )
    (net (code "104") (name "unconnected-(J10-Pad15)") (class "Default")
      (node (ref "J10") (pin "15") (pinfunction "15_15") (pintype "passive"))
    )
    (net (code "105") (name "unconnected-(J10-Pad16)") (class "Default")
      (node (ref "J10") (pin "16") (pinfunction "16_16") (pintype "passive"))
    )
    (net (code "106") (name "unconnected-(J11-Pad1)") (class "Default")
      (node (ref "J11") (pin "1") (pinfunction "1_1") (pintype "passive"))
    )
    (net (code "107") (name "unconnected-(J11-Pad2)") (class "Default")
      (node (ref "J11") (pin "2") (pinfunction "2_2") (pintype "passive"))
    )
    (net (code "108") (name "unconnected-(J11-Pad3)") (class "Default")
      (node (ref "J11") (pin "3") (pinfunction "3_3") (pintype "passive"))
    )
    (net (code "109") (name "unconnected-(J11-Pad4)") (class "Default")
      (node (ref "J11") (pin "4") (pinfunction "4_4") (pintype "passive"))
    )
    (net (code "110") (name "unconnected-(J11-Pad5)") (class "Default")
      (node (ref "J11") (pin "5") (pinfunction "5_5") (pintype "passive"))
    )
    (net (code "111") (name "unconnected-(J11-Pad6)") (class "Default")
      (node (ref "J11") (pin "6") (pinfunction "6_6") (pintype "passive"))
    )
    (net (code "112") (name "unconnected-(J11-Pad7)") (class "Default")
      (node (ref "J11") (pin "7") (pinfunction "7_7") (pintype "passive"))
    )
    (net (code "113") (name "unconnected-(J11-Pad8)") (class "Default")
      (node (ref "J11") (pin "8") (pinfunction "8_8") (pintype "passive"))
    )
    (net (code "114") (name "unconnected-(J11-Pad9)") (class "Default")
      (node (ref "J11") (pin "9") (pinfunction "9_9") (pintype "passive"))
    )
    (net (code "115") (name "unconnected-(J11-Pad10)") (class "Default")
      (node (ref "J11") (pin "10") (pinfunction "10_10") (pintype "passive"))
    )
    (net (code "116") (name "unconnected-(J11-Pad11)") (class "Default")
      (node (ref "J11") (pin "11") (pinfunction "11_11") (pintype "passive"))
    )
    (net (code "117") (name "unconnected-(J11-Pad12)") (class "Default")
      (node (ref "J11") (pin "12") (pinfunction "12_12") (pintype "passive"))
    )
    (net (code "118") (name "unconnected-(J11-Pad13)") (class "Default")
      (node (ref "J11") (pin "13") (pinfunction "13_13") (pintype "passive"))
    )
    (net (code "119") (name "unconnected-(J11-Pad14)") (class "Default")
      (node (ref "J11") (pin "14") (pinfunction "14_14") (pintype "passive"))
    )
    (net (code "120") (name "unconnected-(J11-Pad15)") (class "Default")
      (node (ref "J11") (pin "15") (pinfunction "15_15") (pintype "passive"))
    )
    (net (code "121") (name "unconnected-(J11-Pad16)") (class "Default")
      (node (ref "J11") (pin "16") (pinfunction "16_16") (pintype "passive"))
    )
    (net (code "122") (name "unconnected-(J12-Pad1)") (class "Default")
      (node (ref "J12") (pin "1") (pinfunction "1_1") (pintype "passive"))
    )
    (net (code "123") (name "unconnected-(J12-Pad2)") (class "Default")
      (node (ref "J12") (pin "2") (pinfunction "2_2") (pintype "passive"))
    )
    (net (code "124") (name "unconnected-(J12-Pad3)") (class "Default")
      (node (ref "J12") (pin "3") (pinfunction "3_3") (pintype "passive"))
    )
    (net (code "125") (name "unconnected-(J12-Pad4)") (class "Default")
      (node (ref "J12") (pin "4") (pinfunction "4_4") (pintype "passive"))
    )
    (net (code "126") (name "unconnected-(J12-Pad5)") (class "Default")
      (node (ref "J12") (pin "5") (pinfunction "5_5") (pintype "passive"))
    )
    (net (code "127") (name "unconnected-(J12-Pad6)") (class "Default")
      (node (ref "J12") (pin "6") (pinfunction "6_6") (pintype "passive"))
    )
    (net (code "128") (name "unconnected-(J12-Pad7)") (class "Default")
      (node (ref "J12") (pin "7") (pinfunction "7_7") (pintype "passive"))
    )
    (net (code "129") (name "unconnected-(J12-Pad8)") (class "Default")
      (node (ref "J12") (pin "8") (pinfunction "8_8") (pintype "passive"))
    )
    (net (code "130") (name "unconnected-(J12-Pad9)") (class "Default")
      (node (ref "J12") (pin "9") (pinfunction "9_9") (pintype "passive"))
    )
    (net (code "131") (name "unconnected-(J12-Pad10)") (class "Default")
      (node (ref "J12") (pin "10") (pinfunction "10_10") (pintype "passive"))
    )
    (net (code "132") (name "unconnected-(J12-Pad11)") (class "Default")
      (node (ref "J12") (pin "11") (pinfunction "11_11") (pintype "passive"))
    )
    (net (code "133") (name "unconnected-(J12-Pad12)") (class "Default")
      (node (ref "J12") (pin "12") (pinfunction "12_12") (pintype "passive"))
    )
    (net (code "134") (name "unconnected-(J12-Pad13)") (class "Default")
      (node (ref "J12") (pin "13") (pinfunction "13_13") (pintype "passive"))
    )
    (net (code "135") (name "unconnected-(J12-Pad14)") (class "Default")
      (node (ref "J12") (pin "14") (pinfunction "14_14") (pintype "passive"))
    )
    (net (code "136") (name "unconnected-(J12-Pad15)") (class "Default")
      (node (ref "J12") (pin "15") (pinfunction "15_15") (pintype "passive"))
    )
    (net (code "137") (name "unconnected-(J12-Pad16)") (class "Default")
      (node (ref "J12") (pin "16") (pinfunction "16_16") (pintype "passive"))
    )
    (net (code "138") (name "unconnected-(J13-Pad1)") (class "Default")
      (node (ref "J13") (pin "1") (pinfunction "1_1") (pintype "passive"))
    )
    (net (code "139") (name "unconnected-(J13-Pad2)") (class "Default")
      (node (ref "J13") (pin "2") (pinfunction "2_2") (pintype "passive"))
    )
    (net (code "140") (name "unconnected-(J13-Pad3)") (class "Default")
      (node (ref "J13") (pin "3") (pinfunction "3_3") (pintype "passive"))
    )
    (net (code "141") (name "unconnected-(J13-Pad4)") (class "Default")
      (node (ref "J13") (pin "4") (pinfunction "4_4") (pintype "passive"))
    )
    (net (code "142") (name "unconnected-(J13-Pad5)") (class "Default")
      (node (ref "J13") (pin "5") (pinfunction "5_5") (pintype "passive"))
    )
    (net (code "143") (name "unconnected-(J13-Pad6)") (class "Default")
      (node (ref "J13") (pin "6") (pinfunction "6_6") (pintype "passive"))
    )
    (net (code "144") (name "unconnected-(J13-Pad7)") (class "Default")
      (node (ref "J13") (pin "7") (pinfunction "7_7") (pintype "passive"))
    )
    (net (code "145") (name "unconnected-(J13-Pad8)") (class "Default")
      (node (ref "J13") (pin "8") (pinfunction "8_8") (pintype "passive"))
    )
    (net (code "146") (name "unconnected-(J13-Pad9)") (class "Default")
      (node (ref "J13") (pin "9") (pinfunction "9_9") (pintype "passive"))
    )
    (net (code "147") (name "unconnected-(J13-Pad10)") (class "Default")
      (node (ref "J13") (pin "10") (pinfunction "10_10") (pintype "passive"))
    )
    (net (code "148") (name "unconnected-(J13-Pad11)") (class "Default")
      (node (ref "J13") (pin "11") (pinfunction "11_11") (pintype "passive"))
    )
    (net (code "149") (name "unconnected-(J13-Pad12)") (class "Default")
      (node (ref "J13") (pin "12") (pinfunction "12_12") (pintype "passive"))
    )
    (net (code "150") (name "unconnected-(J13-Pad13)") (class "Default")
      (node (ref "J13") (pin "13") (pinfunction "13_13") (pintype "passive"))
    )
    (net (code "151") (name "unconnected-(J13-Pad14)") (class "Default")
      (node (ref "J13") (pin "14") (pinfunction "14_14") (pintype "passive"))
    )
    (net (code "152") (name "unconnected-(J13-Pad15)") (class "Default")
      (node (ref "J13") (pin "15") (pinfunction "15_15") (pintype "passive"))
    )
    (net (code "153") (name "unconnected-(J13-Pad16)") (class "Default")
      (node (ref "J13") (pin "16") (pinfunction "16_16") (pintype "passive"))
    )
    (net (code "154") (name "unconnected-(J14-Pad1)") (class "Default")
      (node (ref "J14") (pin "1") (pinfunction "1_1") (pintype "passive"))
    )
    (net (code "155") (name "unconnected-(J14-Pad2)") (class "Default")
      (node (ref "J14") (pin "2") (pinfunction "2_2") (pintype "passive"))
    )
    (net (code "156") (name "unconnected-(J14-Pad3)") (class "Default")
      (node (ref "J14") (pin "3") (pinfunction "3_3") (pintype "passive"))
    )
    (net (code "157") (name "unconnected-(J14-Pad4)") (class "Default")
      (node (ref "J14") (pin "4") (pinfunction "4_4") (pintype "passive"))
    )
    (net (code "158") (name "unconnected-(J14-Pad5)") (class "Default")
      (node (ref "J14") (pin "5") (pinfunction "5_5") (pintype "passive"))
    )
    (net (code "159") (name "unconnected-(J14-Pad6)") (class "Default")
      (node (ref "J14") (pin "6") (pinfunction "6_6") (pintype "passive"))
    )
    (net (code "160") (name "unconnected-(J14-Pad7)") (class "Default")
      (node (ref "J14") (pin "7") (pinfunction "7_7") (pintype "passive"))
    )
    (net (code "161") (name "unconnected-(J14-Pad8)") (class "Default")
      (node (ref "J14") (pin "8") (pinfunction "8_8") (pintype "passive"))
    )
    (net (code "162") (name "unconnected-(J14-Pad9)") (class "Default")
      (node (ref "J14") (pin "9") (pinfunction "9_9") (pintype "passive"))
    )
    (net (code "163") (name "unconnected-(J14-Pad10)") (class "Default")
      (node (ref "J14") (pin "10") (pinfunction "10_10") (pintype "passive"))
    )
    (net (code "164") (name "unconnected-(J14-Pad11)") (class "Default")
      (node (ref "J14") (pin "11") (pinfunction "11_11") (pintype "passive"))
    )
    (net (code "165") (name "unconnected-(J14-Pad12)") (class "Default")
      (node (ref "J14") (pin "12") (pinfunction "12_12") (pintype "passive"))
    )
    (net (code "166") (name "unconnected-(J14-Pad13)") (class "Default")
      (node (ref "J14") (pin "13") (pinfunction "13_13") (pintype "passive"))
    )
    (net (code "167") (name "unconnected-(J14-Pad14)") (class "Default")
      (node (ref "J14") (pin "14") (pinfunction "14_14") (pintype "passive"))
    )
    (net (code "168") (name "unconnected-(J14-Pad15)") (class "Default")
      (node (ref "J14") (pin "15") (pinfunction "15_15") (pintype "passive"))
    )
    (net (code "169") (name "unconnected-(J14-Pad16)") (class "Default")
      (node (ref "J14") (pin "16") (pinfunction "16_16") (pintype "passive"))
    )
    (net (code "170") (name "unconnected-(J15-Pad1)") (class "Default")
      (node (ref "J15") (pin "1") (pinfunction "1_1") (pintype "passive"))
    )
    (net (code "171") (name "unconnected-(J15-Pad2)") (class "Default")
      (node (ref "J15") (pin "2") (pinfunction "2_2") (pintype "passive"))
    )
    (net (code "172") (name "unconnected-(J15-Pad3)") (class "Default")
      (node (ref "J15") (pin "3") (pinfunction "3_3") (pintype "passive"))
    )
    (net (code "173") (name "unconnected-(J15-Pad4)") (class "Default")
      (node (ref "J15") (pin "4") (pinfunction "4_4") (pintype "passive"))
    )
    (net (code "174") (name "unconnected-(J15-Pad5)") (class "Default")
      (node (ref "J15") (pin "5") (pinfunction "5_5") (pintype "passive"))
    )
    (net (code "175") (name "unconnected-(J15-Pad6)") (class "Default")
      (node (ref "J15") (pin "6") (pinfunction "6_6") (pintype "passive"))
    )
    (net (code "176") (name "unconnected-(J15-Pad7)") (class "Default")
      (node (ref "J15") (pin "7") (pinfunction "7_7") (pintype "passive"))
    )
    (net (code "177") (name "unconnected-(J15-Pad8)") (class "Default")
      (node (ref "J15") (pin "8") (pinfunction "8_8") (pintype "passive"))
    )
    (net (code "178") (name "unconnected-(J15-Pad9)") (class "Default")
      (node (ref "J15") (pin "9") (pinfunction "9_9") (pintype "passive"))
    )
    (net (code "179") (name "unconnected-(J15-Pad10)") (class "Default")
      (node (ref "J15") (pin "10") (pinfunction "10_10") (pintype "passive"))
    )
    (net (code "180") (name "unconnected-(J15-Pad11)") (class "Default")
      (node (ref "J15") (pin "11") (pinfunction "11_11") (pintype "passive"))
    )
    (net (code "181") (name "unconnected-(J15-Pad12)") (class "Default")
      (node (ref "J15") (pin "12") (pinfunction "12_12") (pintype "passive"))
    )
    (net (code "182") (name "unconnected-(J15-Pad13)") (class "Default")
      (node (ref "J15") (pin "13") (pinfunction "13_13") (pintype "passive"))
    )
    (net (code "183") (name "unconnected-(J15-Pad14)") (class "Default")
      (node (ref "J15") (pin "14") (pinfunction "14_14") (pintype "passive"))
    )
    (net (code "184") (name "unconnected-(J15-Pad15)") (class "Default")
      (node (ref "J15") (pin "15") (pinfunction "15_15") (pintype "passive"))
    )
    (net (code "185") (name "unconnected-(J15-Pad16)") (class "Default")
      (node (ref "J15") (pin "16") (pinfunction "16_16") (pintype "passive"))
    )
    (net (code "186") (name "unconnected-(J16-Pad1)") (class "Default")
      (node (ref "J16") (pin "1") (pinfunction "1_1") (pintype "passive"))
    )
    (net (code "187") (name "unconnected-(J16-Pad2)") (class "Default")
      (node (ref "J16") (pin "2") (pinfunction "2_2") (pintype "passive"))
    )
    (net (code "188") (name "unconnected-(J16-Pad3)") (class "Default")
      (node (ref "J16") (pin "3") (pinfunction "3_3") (pintype "passive"))
    )
    (net (code "189") (name "unconnected-(J16-Pad4)") (class "Default")
      (node (ref "J16") (pin "4") (pinfunction "4_4") (pintype "passive"))
    )
    (net (code "190") (name "unconnected-(J16-Pad5)") (class "Default")
      (node (ref "J16") (pin "5") (pinfunction "5_5") (pintype "passive"))
    )
    (net (code "191") (name "unconnected-(J16-Pad6)") (class "Default")
      (node (ref "J16") (pin "6") (pinfunction "6_6") (pintype "passive"))
    )
    (net (code "192") (name "unconnected-(J16-Pad7)") (class "Default")
      (node (ref "J16") (pin "7") (pinfunction "7_7") (pintype "passive"))
    )
    (net (code "193") (name "unconnected-(J16-Pad8)") (class "Default")
      (node (ref "J16") (pin "8") (pinfunction "8_8") (pintype "passive"))
    )
    (net (code "194") (name "unconnected-(J16-Pad9)") (class "Default")
      (node (ref "J16") (pin "9") (pinfunction "9_9") (pintype "passive"))
    )
    (net (code "195") (name "unconnected-(J16-Pad10)") (class "Default")
      (node (ref "J16") (pin "10") (pinfunction "10_10") (pintype "passive"))
    )
    (net (code "196") (name "unconnected-(J16-Pad11)") (class "Default")
      (node (ref "J16") (pin "11") (pinfunction "11_11") (pintype "passive"))
    )
    (net (code "197") (name "unconnected-(J16-Pad12)") (class "Default")
      (node (ref "J16") (pin "12") (pinfunction "12_12") (pintype "passive"))
    )
    (net (code "198") (name "unconnected-(J16-Pad13)") (class "Default")
      (node (ref "J16") (pin "13") (pinfunction "13_13") (pintype "passive"))
    )
    (net (code "199") (name "unconnected-(J16-Pad14)") (class "Default")
      (node (ref "J16") (pin "14") (pinfunction "14_14") (pintype "passive"))
    )
    (net (code "200") (name "unconnected-(J16-Pad15)") (class "Default")
      (node (ref "J16") (pin "15") (pinfunction "15_15") (pintype "passive"))
    )
    (net (code "201") (name "unconnected-(J16-Pad16)") (class "Default")
      (node (ref "J16") (pin "16") (pinfunction "16_16") (pintype "passive"))
    )
    (net (code "202") (name "unconnected-(J17-Pad1)") (class "Default")
      (node (ref "J17") (pin "1") (pinfunction "1_1") (pintype "passive"))
    )
    (net (code "203") (name "unconnected-(J17-Pad2)") (class "Default")
      (node (ref "J17") (pin "2") (pinfunction "2_2") (pintype "passive"))
    )
    (net (code "204") (name "unconnected-(J17-Pad3)") (class "Default")
      (node (ref "J17") (pin "3") (pinfunction "3_3") (pintype "passive"))
    )
    (net (code "205") (name "unconnected-(J17-Pad4)") (class "Default")
      (node (ref "J17") (pin "4") (pinfunction "4_4") (pintype "passive"))
    )
    (net (code "206") (name "unconnected-(J17-Pad5)") (class "Default")
      (node (ref "J17") (pin "5") (pinfunction "5_5") (pintype "passive"))
    )
    (net (code "207") (name "unconnected-(J17-Pad6)") (class "Default")
      (node (ref "J17") (pin "6") (pinfunction "6_6") (pintype "passive"))
    )
    (net (code "208") (name "unconnected-(J17-Pad7)") (class "Default")
      (node (ref "J17") (pin "7") (pinfunction "7_7") (pintype "passive"))
    )
    (net (code "209") (name "unconnected-(J17-Pad8)") (class "Default")
      (node (ref "J17") (pin "8") (pinfunction "8_8") (pintype "passive"))
    )
    (net (code "210") (name "unconnected-(J17-Pad9)") (class "Default")
      (node (ref "J17") (pin "9") (pinfunction "9_9") (pintype "passive"))
    )
    (net (code "211") (name "unconnected-(J17-Pad10)") (class "Default")
      (node (ref "J17") (pin "10") (pinfunction "10_10") (pintype "passive"))
    )
    (net (code "212") (name "unconnected-(J17-Pad11)") (class "Default")
      (node (ref "J17") (pin "11") (pinfunction "11_11") (pintype "passive"))
    )
    (net (code "213") (name "unconnected-(J17-Pad12)") (class "Default")
      (node (ref "J17") (pin "12") (pinfunction "12_12") (pintype "passive"))
    )
    (net (code "214") (name "unconnected-(J17-Pad13)") (class "Default")
      (node (ref "J17") (pin "13") (pinfunction "13_13") (pintype "passive"))
    )
    (net (code "215") (name "unconnected-(J17-Pad14)") (class "Default")
      (node (ref "J17") (pin "14") (pinfunction "14_14") (pintype "passive"))
    )
    (net (code "216") (name "unconnected-(J17-Pad15)") (class "Default")
      (node (ref "J17") (pin "15") (pinfunction "15_15") (pintype "passive"))
    )
    (net (code "217") (name "unconnected-(J17-Pad16)") (class "Default")
      (node (ref "J17") (pin "16") (pinfunction "16_16") (pintype "passive"))
    )
    (net (code "218") (name "unconnected-(J18-Pad1)") (class "Default")
      (node (ref "J18") (pin "1") (pinfunction "1_1") (pintype "passive"))
    )
    (net (code "219") (name "unconnected-(J18-Pad2)") (class "Default")
      (node (ref "J18") (pin "2") (pinfunction "2_2") (pintype "passive"))
    )
    (net (code "220") (name "unconnected-(J18-Pad3)") (class "Default")
      (node (ref "J18") (pin "3") (pinfunction "3_3") (pintype "passive"))
    )
    (net (code "221") (name "unconnected-(J18-Pad4)") (class "Default")
      (node (ref "J18") (pin "4") (pinfunction "4_4") (pintype "passive"))
    )
    (net (code "222") (name "unconnected-(J18-Pad5)") (class "Default")
      (node (ref "J18") (pin "5") (pinfunction "5_5") (pintype "passive"))
    )
    (net (code "223") (name "unconnected-(J18-Pad6)") (class "Default")
      (node (ref "J18") (pin "6") (pinfunction "6_6") (pintype "passive"))
    )
    (net (code "224") (name "unconnected-(J18-Pad7)") (class "Default")
      (node (ref "J18") (pin "7") (pinfunction "7_7") (pintype "passive"))
    )
    (net (code "225") (name "unconnected-(J18-Pad8)") (class "Default")
      (node (ref "J18") (pin "8") (pinfunction "8_8") (pintype "passive"))
    )
    (net (code "226") (name "unconnected-(J18-Pad9)") (class "Default")
      (node (ref "J18") (pin "9") (pinfunction "9_9") (pintype "passive"))
    )
    (net (code "227") (name "unconnected-(J18-Pad10)") (class "Default")
      (node (ref "J18") (pin "10") (pinfunction "10_10") (pintype "passive"))
    )
    (net (code "228") (name "unconnected-(J18-Pad11)") (class "Default")
      (node (ref "J18") (pin "11") (pinfunction "11_11") (pintype "passive"))
    )
    (net (code "229") (name "unconnected-(J18-Pad12)") (class "Default")
      (node (ref "J18") (pin "12") (pinfunction "12_12") (pintype "passive"))
    )
    (net (code "230") (name "unconnected-(J18-Pad13)") (class "Default")
      (node (ref "J18") (pin "13") (pinfunction "13_13") (pintype "passive"))
    )
    (net (code "231") (name "unconnected-(J18-Pad14)") (class "Default")
      (node (ref "J18") (pin "14") (pinfunction "14_14") (pintype "passive"))
    )
    (net (code "232") (name "unconnected-(J18-Pad15)") (class "Default")
      (node (ref "J18") (pin "15") (pinfunction "15_15") (pintype "passive"))
    )
    (net (code "233") (name "unconnected-(J18-Pad16)") (class "Default")
      (node (ref "J18") (pin "16") (pinfunction "16_16") (pintype "passive"))
    )
    (net (code "234") (name "unconnected-(J19-Pad1)") (class "Default")
      (node (ref "J19") (pin "1") (pinfunction "1_1") (pintype "passive"))
    )
    (net (code "235") (name "unconnected-(J19-Pad2)") (class "Default")
      (node (ref "J19") (pin "2") (pinfunction "2_2") (pintype "passive"))
    )
    (net (code "236") (name "unconnected-(J19-Pad3)") (class "Default")
      (node (ref "J19") (pin "3") (pinfunction "3_3") (pintype "passive"))
    )
    (net (code "237") (name "unconnected-(J19-Pad4)") (class "Default")
      (node (ref "J19") (pin "4") (pinfunction "4_4") (pintype "passive"))
    )
    (net (code "238") (name "unconnected-(J19-Pad5)") (class "Default")
      (node (ref "J19") (pin "5") (pinfunction "5_5") (pintype "passive"))
    )
    (net (code "239") (name "unconnected-(J19-Pad6)") (class "Default")
      (node (ref "J19") (pin "6") (pinfunction "6_6") (pintype "passive"))
    )
    (net (code "240") (name "unconnected-(J19-Pad7)") (class "Default")
      (node (ref "J19") (pin "7") (pinfunction "7_7") (pintype "passive"))
    )
    (net (code "241") (name "unconnected-(J19-Pad8)") (class "Default")
      (node (ref "J19") (pin "8") (pinfunction "8_8") (pintype "passive"))
    )
    (net (code "242") (name "unconnected-(J19-Pad9)") (class "Default")
      (node (ref "J19") (pin "9") (pinfunction "9_9") (pintype "passive"))
    )
    (net (code "243") (name "unconnected-(J19-Pad10)") (class "Default")
      (node (ref "J19") (pin "10") (pinfunction "10_10") (pintype "passive"))
    )
    (net (code "244") (name "unconnected-(J19-Pad11)") (class "Default")
      (node (ref "J19") (pin "11") (pinfunction "11_11") (pintype "passive"))
    )
    (net (code "245") (name "unconnected-(J19-Pad12)") (class "Default")
      (node (ref "J19") (pin "12") (pinfunction "12_12") (pintype "passive"))
    )
    (net (code "246") (name "unconnected-(J19-Pad13)") (class "Default")
      (node (ref "J19") (pin "13") (pinfunction "13_13") (pintype "passive"))
    )
    (net (code "247") (name "unconnected-(J19-Pad14)") (class "Default")
      (node (ref "J19") (pin "14") (pinfunction "14_14") (pintype "passive"))
    )
    (net (code "248") (name "unconnected-(J19-Pad15)") (class "Default")
      (node (ref "J19") (pin "15") (pinfunction "15_15") (pintype "passive"))
    )
    (net (code "249") (name "unconnected-(J19-Pad16)") (class "Default")
      (node (ref "J19") (pin "16") (pinfunction "16_16") (pintype "passive"))
    )
    (net (code "250") (name "unconnected-(J20-Pad1)") (class "Default")
      (node (ref "J20") (pin "1") (pinfunction "1_1") (pintype "passive"))
    )
    (net (code "251") (name "unconnected-(J20-Pad2)") (class "Default")
      (node (ref "J20") (pin "2") (pinfunction "2_2") (pintype "passive"))
    )
    (net (code "252") (name "unconnected-(J20-Pad3)") (class "Default")
      (node (ref "J20") (pin "3") (pinfunction "3_3") (pintype "passive"))
    )
    (net (code "253") (name "unconnected-(J20-Pad4)") (class "Default")
      (node (ref "J20") (pin "4") (pinfunction "4_4") (pintype "passive"))
    )
    (net (code "254") (name "unconnected-(J20-Pad5)") (class "Default")
      (node (ref "J20") (pin "5") (pinfunction "5_5") (pintype "passive"))
    )
    (net (code "255") (name "unconnected-(J20-Pad6)") (class "Default")
      (node (ref "J20") (pin "6") (pinfunction "6_6") (pintype "passive"))
    )
    (net (code "256") (name "unconnected-(J20-Pad7)") (class "Default")
      (node (ref "J20") (pin "7") (pinfunction "7_7") (pintype "passive"))
    )
    (net (code "257") (name "unconnected-(J20-Pad8)") (class "Default")
      (node (ref "J20") (pin "8") (pinfunction "8_8") (pintype "passive"))
    )
    (net (code "258") (name "unconnected-(J20-Pad9)") (class "Default")
      (node (ref "J20") (pin "9") (pinfunction "9_9") (pintype "passive"))
    )
    (net (code "259") (name "unconnected-(J20-Pad10)") (class "Default")
      (node (ref "J20") (pin "10") (pinfunction "10_10") (pintype "passive"))
    )
    (net (code "260") (name "unconnected-(J20-Pad11)") (class "Default")
      (node (ref "J20") (pin "11") (pinfunction "11_11") (pintype "passive"))
    )
    (net (code "261") (name "unconnected-(J20-Pad12)") (class "Default")
      (node (ref "J20") (pin "12") (pinfunction "12_12") (pintype "passive"))
    )
    (net (code "262") (name "unconnected-(J20-Pad13)") (class "Default")
      (node (ref "J20") (pin "13") (pinfunction "13_13") (pintype "passive"))
    )
    (net (code "263") (name "unconnected-(J20-Pad14)") (class "Default")
      (node (ref "J20") (pin "14") (pinfunction "14_14") (pintype "passive"))
    )
    (net (code "264") (name "unconnected-(J20-Pad15)") (class "Default")
      (node (ref "J20") (pin "15") (pinfunction "15_15") (pintype "passive"))
    )
    (net (code "265") (name "unconnected-(J20-Pad16)") (class "Default")
      (node (ref "J20") (pin "16") (pinfunction "16_16") (pintype "passive"))
    )
    (net (code "266") (name "unconnected-(J21-Pad1)") (class "Default")
      (node (ref "J21") (pin "1") (pinfunction "1_1") (pintype "passive"))
    )
    (net (code "267") (name "unconnected-(J21-Pad2)") (class "Default")
      (node (ref "J21") (pin "2") (pinfunction "2_2") (pintype "passive"))
    )
    (net (code "268") (name "unconnected-(J21-Pad3)") (class "Default")
      (node (ref "J21") (pin "3") (pinfunction "3_3") (pintype "passive"))
    )
    (net (code "269") (name "unconnected-(J21-Pad4)") (class "Default")
      (node (ref "J21") (pin "4") (pinfunction "4_4") (pintype "passive"))
    )
    (net (code "270") (name "unconnected-(J21-Pad5)") (class "Default")
      (node (ref "J21") (pin "5") (pinfunction "5_5") (pintype "passive"))
    )
    (net (code "271") (name "unconnected-(J21-Pad6)") (class "Default")
      (node (ref "J21") (pin "6") (pinfunction "6_6") (pintype "passive"))
    )
    (net (code "272") (name "unconnected-(J21-Pad7)") (class "Default")
      (node (ref "J21") (pin "7") (pinfunction "7_7") (pintype "passive"))
    )
    (net (code "273") (name "unconnected-(J21-Pad8)") (class "Default")
      (node (ref "J21") (pin "8") (pinfunction "8_8") (pintype "passive"))
    )
    (net (code "274") (name "unconnected-(J21-Pad9)") (class "Default")
      (node (ref "J21") (pin "9") (pinfunction "9_9") (pintype "passive"))
    )
    (net (code "275") (name "unconnected-(J21-Pad10)") (class "Default")
      (node (ref "J21") (pin "10") (pinfunction "10_10") (pintype "passive"))
    )
    (net (code "276") (name "unconnected-(J21-Pad11)") (class "Default")
      (node (ref "J21") (pin "11") (pinfunction "11_11") (pintype "passive"))
    )
    (net (code "277") (name "unconnected-(J21-Pad12)") (class "Default")
      (node (ref "J21") (pin "12") (pinfunction "12_12") (pintype "passive"))
    )
    (net (code "278") (name "unconnected-(J21-Pad13)") (class "Default")
      (node (ref "J21") (pin "13") (pinfunction "13_13") (pintype "passive"))
    )
    (net (code "279") (name "unconnected-(J21-Pad14)") (class "Default")
      (node (ref "J21") (pin "14") (pinfunction "14_14") (pintype "passive"))
    )
    (net (code "280") (name "unconnected-(J21-Pad15)") (class "Default")
      (node (ref "J21") (pin "15") (pinfunction "15_15") (pintype "passive"))
    )
    (net (code "281") (name "unconnected-(J21-Pad16)") (class "Default")
      (node (ref "J21") (pin "16") (pinfunction "16_16") (pintype "passive"))
    )
  )
)
